# 3V8_Buck_Boost_Converter.net
KiCad netlist of a schematic drawn in Altium Designer
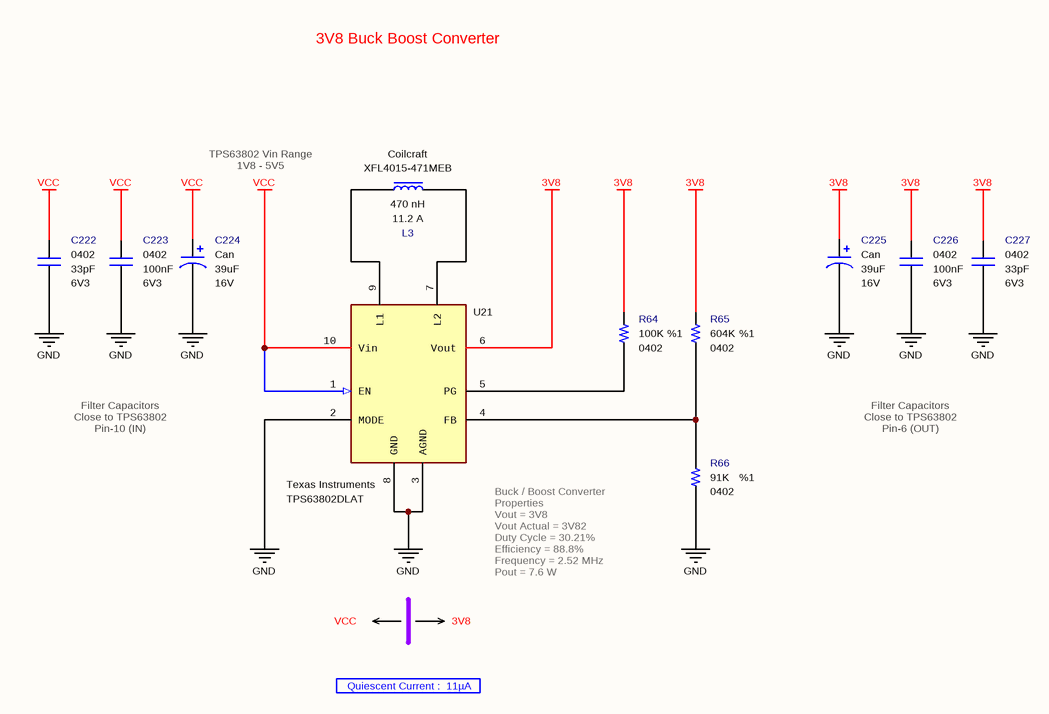
[diagram p0: 3V8 Buck Boost Converter.SchDoc]

(export (version "E")
  (design (tool "Eeschema 10.0.6"))
  (components
    (comp (ref "C222")
      (value "33pF")
      (footprint "CAPACITOR_0402")
      (description "Capacitor - 33pF [0402] (Ceramic)")
      (fields
        (field (name "MANUFACTURER PART NUMBER") "C0402C330J9RACAUTO")
        (field (name "MOUSER PART NUMBER") "80-C0402C330J9RAUTO")
        (field (name "CASE") "0402")
        (field (name "VOLTAGE") "6V3")
      )
      (libsource (lib "Ovoo_Library") (part "Capacitor - 33pF [0402-6V3]"))
    )
    (comp (ref "C223")
      (value "100nF")
      (footprint "CAPACITOR_0402")
      (description "Capacitor - 100nF [0402-6V3] (Ceramic)")
      (fields
        (field (name "CASE") "0402")
        (field (name "TOLERANCE") "%10")
        (field (name "VOLTAGE") "6V3")
        (field (name "MANUFACTURER PART NUMBER") "04026D104KAT4A")
      )
      (libsource (lib "Ovoo_Library") (part "Capacitor - 100nF [0402-6V3]"))
    )
    (comp (ref "C224")
      (value "39uF")
      (footprint "CAPACITOR_CAN-B6")
      (description "Capacitor - 39uF 16V [Can] (Electrolytic)")
      (fields
        (field (name "TOLERANCE") "20%")
        (field (name "CASE") "Can")
        (field (name "VOLTAGE") "16V")
        (field (name "MANUFACTURER PART NUMBER") "16SVPC39MV")
      )
      (libsource (lib "Ovoo_Library") (part "Capacitor - 39uF [Can-16V]"))
    )
    (comp (ref "C225")
      (value "39uF")
      (footprint "CAPACITOR_CAN-B6")
      (description "Capacitor - 39uF 16V [Can] (Electrolytic)")
      (fields
        (field (name "TOLERANCE") "20%")
        (field (name "CASE") "Can")
        (field (name "VOLTAGE") "16V")
        (field (name "MANUFACTURER PART NUMBER") "16SVPC39MV")
      )
      (libsource (lib "Ovoo_Library") (part "Capacitor - 39uF [Can-16V]"))
    )
    (comp (ref "C226")
      (value "100nF")
      (footprint "CAPACITOR_0402")
      (description "Capacitor - 100nF [0402-6V3] (Ceramic)")
      (fields
        (field (name "CASE") "0402")
        (field (name "TOLERANCE") "%10")
        (field (name "VOLTAGE") "6V3")
        (field (name "MANUFACTURER PART NUMBER") "04026D104KAT4A")
      )
      (libsource (lib "Ovoo_Library") (part "Capacitor - 100nF [0402-6V3]"))
    )
    (comp (ref "C227")
      (value "33pF")
      (footprint "CAPACITOR_0402")
      (description "Capacitor - 33pF [0402] (Ceramic)")
      (fields
        (field (name "TOLERANCE") "10%")
        (field (name "CASE") "0402")
        (field (name "VOLTAGE") "6V3")
        (field (name "MANUFACTURER PART NUMBER") "C0402C330J9RACAUTO")
      )
      (libsource (lib "Ovoo_Library") (part "Capacitor - 33pF [0402-6V3]"))
    )
    (comp (ref "L3")
      (value "470 nH")
      (footprint "INDUCTOR_XFL4015")
      (description "Fixed Inductors 0.47uH 20% 11.2A 8.36mOhms AEC-Q200")
      (fields
        (field (name "TOLERANCE") "20%")
        (field (name "MAXIMUM DC CURRENT") "11.2 A")
        (field (name "MOUSER PART NUMBER") "994-XFL4015-471MEB")
        (field (name "MANUFACTURER PART NUMBER") "XFL4015-471MEB")
        (field (name "MANUFACTURER NAME") "Coilcraft")
      )
      (libsource (lib "Ovoo_Library") (part "Inductor - 470 nH [SMD]"))
    )
    (comp (ref "R64")
      (value "100K")
      (footprint "RESISTOR_0402")
      (description "Thick Film Resistors - SMD 1/16 W 100 Kohms 1%")
      (fields
        (field (name "TOLERANCE") "%1")
        (field (name "CASE") "0402")
        (field (name "MANUFACTURER PART NUMBER") "CRCW0402100KFKED")
        (field (name "MOUSER PART NUMBER") "71-CRCW0402-100K-E3")
      )
      (libsource (lib "Ovoo_Library") (part "Resistor - 100K"))
    )
    (comp (ref "R65")
      (value "604K")
      (footprint "RESISTOR_0402")
      (description "Thick Film Resistors - SMD 1/16 W 604 Kohms 1%")
      (fields
        (field (name "TOLERANCE") "%1")
        (field (name "CASE") "0402")
        (field (name "MANUFACTURER PART NUMBER") "CRCW0402604KFKED")
        (field (name "MOUSER PART NUMBER") "71-CRCW0402-604K-E3")
      )
      (libsource (lib "Ovoo_Library") (part "Resistor - 604K"))
    )
    (comp (ref "R66")
      (value "91K")
      (footprint "RESISTOR_0402")
      (description "Thick Film Resistors - SMD 1/16 W 91 Kohms 1%")
      (fields
        (field (name "TOLERANCE") "%1")
        (field (name "CASE") "0402")
        (field (name "MANUFACTURER PART NUMBER") "CRCW040291K0FKED")
        (field (name "MOUSER PART NUMBER") "71-CRCW040291K0FKED")
      )
      (libsource (lib "Ovoo_Library") (part "Resistor - 91K"))
    )
    (comp (ref "U21")
      (value "Buck-Boost Converter")
      (footprint "VSON-10")
      (fields
        (field (name "MOUSER PART NUMBER") "595-TPS63802DLAT")
        (field (name "MANUFACTURER PART NUMBER") "TPS63802DLAT")
        (field (name "MANUFACTURER NAME") "Texas Instruments")
      )
      (libsource (lib "Ovoo_Library") (part "IC - TPS63802DLAT"))
    )
  )
  (nets
    (net (code "1") (name "3V8") (class "Default")
      (node (ref "C225") (pin "1") (pinfunction "1_1") (pintype "passive"))
      (node (ref "C226") (pin "1") (pinfunction "1_1") (pintype "passive"))
      (node (ref "C227") (pin "2") (pinfunction "2_2") (pintype "passive"))
      (node (ref "R64") (pin "2") (pinfunction "2_2") (pintype "passive"))
      (node (ref "R65") (pin "2") (pinfunction "2_2") (pintype "passive"))
      (node (ref "U21") (pin "6") (pinfunction "Vout_6") (pintype "power_in"))
    )
    (net (code "2") (name "GND") (class "Default")
      (node (ref "C222") (pin "1") (pinfunction "1_1") (pintype "passive"))
      (node (ref "C223") (pin "2") (pinfunction "2_2") (pintype "passive"))
      (node (ref "C224") (pin "2") (pinfunction "2_2") (pintype "passive"))
      (node (ref "C225") (pin "2") (pinfunction "2_2") (pintype "passive"))
      (node (ref "C226") (pin "2") (pinfunction "2_2") (pintype "passive"))
      (node (ref "C227") (pin "1") (pinfunction "1_1") (pintype "passive"))
      (node (ref "R66") (pin "1") (pinfunction "1_1") (pintype "passive"))
      (node (ref "U21") (pin "2") (pinfunction "MODE_2") (pintype "passive"))
      (node (ref "U21") (pin "3") (pinfunction "AGND_3") (pintype "power_in"))
      (node (ref "U21") (pin "8") (pinfunction "GND_8") (pintype "power_in"))
    )
    (net (code "3") (name "Net-(U21-FB)") (class "Default")
      (node (ref "R65") (pin "1") (pinfunction "1_1") (pintype "passive"))
      (node (ref "R66") (pin "2") (pinfunction "2_2") (pintype "passive"))
      (node (ref "U21") (pin "4") (pinfunction "FB_4") (pintype "passive"))
    )
    (net (code "4") (name "Net-(U21-L1)") (class "Default")
      (node (ref "L3") (pin "1") (pinfunction "1_1") (pintype "passive"))
      (node (ref "U21") (pin "9") (pinfunction "L1_9") (pintype "passive"))
    )
    (net (code "5") (name "Net-(U21-L2)") (class "Default")
      (node (ref "L3") (pin "2") (pinfunction "2_2") (pintype "passive"))
      (node (ref "U21") (pin "7") (pinfunction "L2_7") (pintype "passive"))
    )
    (net (code "6") (name "Net-(U21-PG)") (class "Default")
      (node (ref "R64") (pin "1") (pinfunction "1_1") (pintype "passive"))
      (node (ref "U21") (pin "5") (pinfunction "PG_5") (pintype "passive"))
    )
    (net (code "7") (name "VCC") (class "Default")
      (node (ref "C222") (pin "2") (pinfunction "2_2") (pintype "passive"))
      (node (ref "C223") (pin "1") (pinfunction "1_1") (pintype "passive"))
      (node (ref "C224") (pin "1") (pinfunction "1_1") (pintype "passive"))
      (node (ref "U21") (pin "1") (pinfunction "EN_1") (pintype "input"))
      (node (ref "U21") (pin "10") (pinfunction "Vin_10") (pintype "power_in"))
    )
  )
)
